# 2_classyTKL_SMK_matrix.net
KiCad netlist of a schematic drawn in Altium Designer
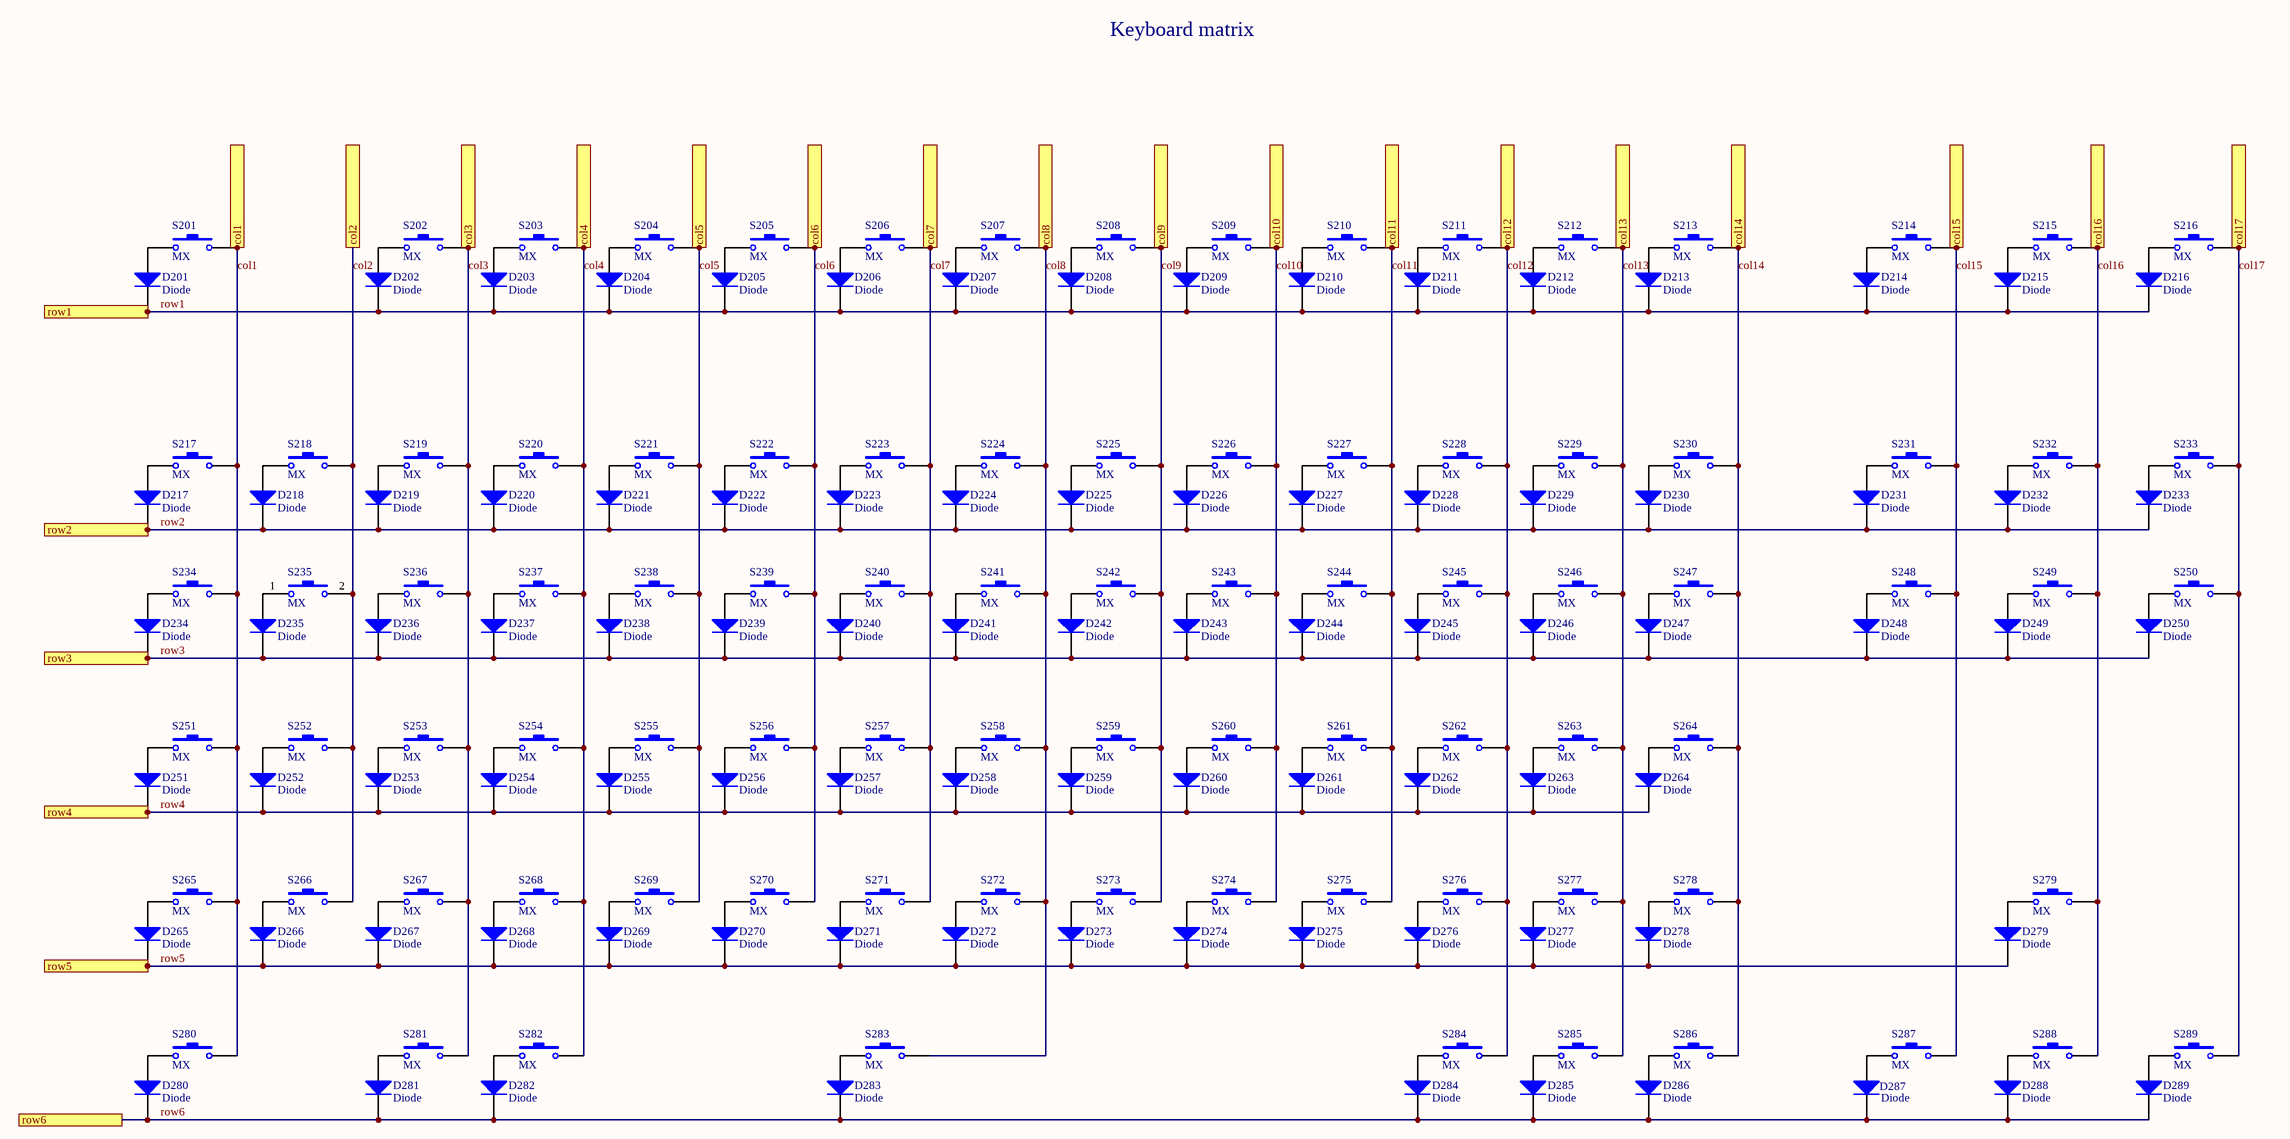
[diagram p0: 2_classyTKL_SMK_matrix.SchDoc]

(export (version "E")
  (design (tool "Eeschema 10.0.6"))
  (components
    (comp (ref "D201")
      (value "Diode")
      (footprint "SOD-123")
      (description "Default Diode")
      (fields (field (name "LCSC PART #") "C81598") (field (name "MRF.PART") "1N4148W"))
      (libsource (lib "Miscellaneous Devices") (part "Diode"))
    )
    (comp (ref "D202")
      (value "Diode")
      (footprint "SOD-123")
      (description "Default Diode")
      (fields (field (name "LCSC PART #") "C81598") (field (name "MRF.PART") "1N4148W"))
      (libsource (lib "Miscellaneous Devices") (part "Diode"))
    )
    (comp (ref "D203")
      (value "Diode")
      (footprint "SOD-123")
      (description "Default Diode")
      (fields (field (name "LCSC PART #") "C81598") (field (name "MRF.PART") "1N4148W"))
      (libsource (lib "Miscellaneous Devices") (part "Diode"))
    )
    (comp (ref "D204")
      (value "Diode")
      (footprint "SOD-123")
      (description "Default Diode")
      (fields (field (name "LCSC PART #") "C81598") (field (name "MRF.PART") "1N4148W"))
      (libsource (lib "Miscellaneous Devices") (part "Diode"))
    )
    (comp (ref "D205")
      (value "Diode")
      (footprint "SOD-123")
      (description "Default Diode")
      (fields (field (name "LCSC PART #") "C81598") (field (name "MRF.PART") "1N4148W"))
      (libsource (lib "Miscellaneous Devices") (part "Diode"))
    )
    (comp (ref "D206")
      (value "Diode")
      (footprint "SOD-123")
      (description "Default Diode")
      (fields (field (name "LCSC PART #") "C81598") (field (name "MRF.PART") "1N4148W"))
      (libsource (lib "Miscellaneous Devices") (part "Diode"))
    )
    (comp (ref "D207")
      (value "Diode")
      (footprint "SOD-123")
      (description "Default Diode")
      (fields (field (name "LCSC PART #") "C81598") (field (name "MRF.PART") "1N4148W"))
      (libsource (lib "Miscellaneous Devices") (part "Diode"))
    )
    (comp (ref "D208")
      (value "Diode")
      (footprint "SOD-123")
      (description "Default Diode")
      (fields (field (name "LCSC PART #") "C81598") (field (name "MRF.PART") "1N4148W"))
      (libsource (lib "Miscellaneous Devices") (part "Diode"))
    )
    (comp (ref "D209")
      (value "Diode")
      (footprint "SOD-123")
      (description "Default Diode")
      (fields (field (name "LCSC PART #") "C81598") (field (name "MRF.PART") "1N4148W"))
      (libsource (lib "Miscellaneous Devices") (part "Diode"))
    )
    (comp (ref "D210")
      (value "Diode")
      (footprint "SOD-123")
      (description "Default Diode")
      (fields (field (name "LCSC PART #") "C81598") (field (name "MRF.PART") "1N4148W"))
      (libsource (lib "Miscellaneous Devices") (part "Diode"))
    )
    (comp (ref "D211")
      (value "Diode")
      (footprint "SOD-123")
      (description "Default Diode")
      (fields (field (name "LCSC PART #") "C81598") (field (name "MRF.PART") "1N4148W"))
      (libsource (lib "Miscellaneous Devices") (part "Diode"))
    )
    (comp (ref "D212")
      (value "Diode")
      (footprint "SOD-123")
      (description "Default Diode")
      (fields (field (name "LCSC PART #") "C81598") (field (name "MRF.PART") "1N4148W"))
      (libsource (lib "Miscellaneous Devices") (part "Diode"))
    )
    (comp (ref "D213")
      (value "Diode")
      (footprint "SOD-123")
      (description "Default Diode")
      (fields (field (name "LCSC PART #") "C81598") (field (name "MRF.PART") "1N4148W"))
      (libsource (lib "Miscellaneous Devices") (part "Diode"))
    )
    (comp (ref "D214")
      (value "Diode")
      (footprint "SOD-123")
      (description "Default Diode")
      (fields (field (name "LCSC PART #") "C81598") (field (name "MRF.PART") "1N4148W"))
      (libsource (lib "Miscellaneous Devices") (part "Diode"))
    )
    (comp (ref "D215")
      (value "Diode")
      (footprint "SOD-123")
      (description "Default Diode")
      (fields (field (name "LCSC PART #") "C81598") (field (name "MRF.PART") "1N4148W"))
      (libsource (lib "Miscellaneous Devices") (part "Diode"))
    )
    (comp (ref "D216")
      (value "Diode")
      (footprint "SOD-123")
      (description "Default Diode")
      (fields (field (name "LCSC PART #") "C81598") (field (name "MRF.PART") "1N4148W"))
      (libsource (lib "Miscellaneous Devices") (part "Diode"))
    )
    (comp (ref "D217")
      (value "Diode")
      (footprint "SOD-123")
      (description "Default Diode")
      (fields (field (name "LCSC PART #") "C81598") (field (name "MRF.PART") "1N4148W"))
      (libsource (lib "Miscellaneous Devices") (part "Diode"))
    )
    (comp (ref "D218")
      (value "Diode")
      (footprint "SOD-123")
      (description "Default Diode")
      (fields (field (name "LCSC PART #") "C81598") (field (name "MRF.PART") "1N4148W"))
      (libsource (lib "Miscellaneous Devices") (part "Diode"))
    )
    (comp (ref "D219")
      (value "Diode")
      (footprint "SOD-123")
      (description "Default Diode")
      (fields (field (name "LCSC PART #") "C81598") (field (name "MRF.PART") "1N4148W"))
      (libsource (lib "Miscellaneous Devices") (part "Diode"))
    )
    (comp (ref "D220")
      (value "Diode")
      (footprint "SOD-123")
      (description "Default Diode")
      (fields (field (name "LCSC PART #") "C81598") (field (name "MRF.PART") "1N4148W"))
      (libsource (lib "Miscellaneous Devices") (part "Diode"))
    )
    (comp (ref "D221")
      (value "Diode")
      (footprint "SOD-123")
      (description "Default Diode")
      (fields (field (name "LCSC PART #") "C81598") (field (name "MRF.PART") "1N4148W"))
      (libsource (lib "Miscellaneous Devices") (part "Diode"))
    )
    (comp (ref "D222")
      (value "Diode")
      (footprint "SOD-123")
      (description "Default Diode")
      (fields (field (name "LCSC PART #") "C81598") (field (name "MRF.PART") "1N4148W"))
      (libsource (lib "Miscellaneous Devices") (part "Diode"))
    )
    (comp (ref "D223")
      (value "Diode")
      (footprint "SOD-123")
      (description "Default Diode")
      (fields (field (name "LCSC PART #") "C81598") (field (name "MRF.PART") "1N4148W"))
      (libsource (lib "Miscellaneous Devices") (part "Diode"))
    )
    (comp (ref "D224")
      (value "Diode")
      (footprint "SOD-123")
      (description "Default Diode")
      (fields (field (name "LCSC PART #") "C81598") (field (name "MRF.PART") "1N4148W"))
      (libsource (lib "Miscellaneous Devices") (part "Diode"))
    )
    (comp (ref "D225")
      (value "Diode")
      (footprint "SOD-123")
      (description "Default Diode")
      (fields (field (name "LCSC PART #") "C81598") (field (name "MRF.PART") "1N4148W"))
      (libsource (lib "Miscellaneous Devices") (part "Diode"))
    )
    (comp (ref "D226")
      (value "Diode")
      (footprint "SOD-123")
      (description "Default Diode")
      (fields (field (name "LCSC PART #") "C81598") (field (name "MRF.PART") "1N4148W"))
      (libsource (lib "Miscellaneous Devices") (part "Diode"))
    )
    (comp (ref "D227")
      (value "Diode")
      (footprint "SOD-123")
      (description "Default Diode")
      (fields (field (name "LCSC PART #") "C81598") (field (name "MRF.PART") "1N4148W"))
      (libsource (lib "Miscellaneous Devices") (part "Diode"))
    )
    (comp (ref "D228")
      (value "Diode")
      (footprint "SOD-123")
      (description "Default Diode")
      (fields (field (name "LCSC PART #") "C81598") (field (name "MRF.PART") "1N4148W"))
      (libsource (lib "Miscellaneous Devices") (part "Diode"))
    )
    (comp (ref "D229")
      (value "Diode")
      (footprint "SOD-123")
      (description "Default Diode")
      (fields (field (name "LCSC PART #") "C81598") (field (name "MRF.PART") "1N4148W"))
      (libsource (lib "Miscellaneous Devices") (part "Diode"))
    )
    (comp (ref "D230")
      (value "Diode")
      (footprint "SOD-123")
      (description "Default Diode")
      (fields (field (name "LCSC PART #") "C81598") (field (name "MRF.PART") "1N4148W"))
      (libsource (lib "Miscellaneous Devices") (part "Diode"))
    )
    (comp (ref "D231")
      (value "Diode")
      (footprint "SOD-123")
      (description "Default Diode")
      (fields (field (name "LCSC PART #") "C81598") (field (name "MRF.PART") "1N4148W"))
      (libsource (lib "Miscellaneous Devices") (part "Diode"))
    )
    (comp (ref "D232")
      (value "Diode")
      (footprint "SOD-123")
      (description "Default Diode")
      (fields (field (name "LCSC PART #") "C81598") (field (name "MRF.PART") "1N4148W"))
      (libsource (lib "Miscellaneous Devices") (part "Diode"))
    )
    (comp (ref "D233")
      (value "Diode")
      (footprint "SOD-123")
      (description "Default Diode")
      (fields (field (name "LCSC PART #") "C81598") (field (name "MRF.PART") "1N4148W"))
      (libsource (lib "Miscellaneous Devices") (part "Diode"))
    )
    (comp (ref "D234")
      (value "Diode")
      (footprint "SOD-123")
      (description "Default Diode")
      (fields (field (name "LCSC PART #") "C81598") (field (name "MRF.PART") "1N4148W"))
      (libsource (lib "Miscellaneous Devices") (part "Diode"))
    )
    (comp (ref "D235")
      (value "Diode")
      (footprint "SOD-123")
      (description "Default Diode")
      (fields (field (name "LCSC PART #") "C81598") (field (name "MRF.PART") "1N4148W"))
      (libsource (lib "Miscellaneous Devices") (part "Diode"))
    )
    (comp (ref "D236")
      (value "Diode")
      (footprint "SOD-123")
      (description "Default Diode")
      (fields (field (name "LCSC PART #") "C81598") (field (name "MRF.PART") "1N4148W"))
      (libsource (lib "Miscellaneous Devices") (part "Diode"))
    )
    (comp (ref "D237")
      (value "Diode")
      (footprint "SOD-123")
      (description "Default Diode")
      (fields (field (name "LCSC PART #") "C81598") (field (name "MRF.PART") "1N4148W"))
      (libsource (lib "Miscellaneous Devices") (part "Diode"))
    )
    (comp (ref "D238")
      (value "Diode")
      (footprint "SOD-123")
      (description "Default Diode")
      (fields (field (name "LCSC PART #") "C81598") (field (name "MRF.PART") "1N4148W"))
      (libsource (lib "Miscellaneous Devices") (part "Diode"))
    )
    (comp (ref "D239")
      (value "Diode")
      (footprint "SOD-123")
      (description "Default Diode")
      (fields (field (name "LCSC PART #") "C81598") (field (name "MRF.PART") "1N4148W"))
      (libsource (lib "Miscellaneous Devices") (part "Diode"))
    )
    (comp (ref "D240")
      (value "Diode")
      (footprint "SOD-123")
      (description "Default Diode")
      (fields (field (name "LCSC PART #") "C81598") (field (name "MRF.PART") "1N4148W"))
      (libsource (lib "Miscellaneous Devices") (part "Diode"))
    )
    (comp (ref "D241")
      (value "Diode")
      (footprint "SOD-123")
      (description "Default Diode")
      (fields (field (name "LCSC PART #") "C81598") (field (name "MRF.PART") "1N4148W"))
      (libsource (lib "Miscellaneous Devices") (part "Diode"))
    )
    (comp (ref "D242")
      (value "Diode")
      (footprint "SOD-123")
      (description "Default Diode")
      (fields (field (name "LCSC PART #") "C81598") (field (name "MRF.PART") "1N4148W"))
      (libsource (lib "Miscellaneous Devices") (part "Diode"))
    )
    (comp (ref "D243")
      (value "Diode")
      (footprint "SOD-123")
      (description "Default Diode")
      (fields (field (name "LCSC PART #") "C81598") (field (name "MRF.PART") "1N4148W"))
      (libsource (lib "Miscellaneous Devices") (part "Diode"))
    )
    (comp (ref "D244")
      (value "Diode")
      (footprint "SOD-123")
      (description "Default Diode")
      (fields (field (name "LCSC PART #") "C81598") (field (name "MRF.PART") "1N4148W"))
      (libsource (lib "Miscellaneous Devices") (part "Diode"))
    )
    (comp (ref "D245")
      (value "Diode")
      (footprint "SOD-123")
      (description "Default Diode")
      (fields (field (name "LCSC PART #") "C81598") (field (name "MRF.PART") "1N4148W"))
      (libsource (lib "Miscellaneous Devices") (part "Diode"))
    )
    (comp (ref "D246")
      (value "Diode")
      (footprint "SOD-123")
      (description "Default Diode")
      (fields (field (name "LCSC PART #") "C81598") (field (name "MRF.PART") "1N4148W"))
      (libsource (lib "Miscellaneous Devices") (part "Diode"))
    )
    (comp (ref "D247")
      (value "Diode")
      (footprint "SOD-123")
      (description "Default Diode")
      (fields (field (name "LCSC PART #") "C81598") (field (name "MRF.PART") "1N4148W"))
      (libsource (lib "Miscellaneous Devices") (part "Diode"))
    )
    (comp (ref "D248")
      (value "Diode")
      (footprint "SOD-123")
      (description "Default Diode")
      (fields (field (name "LCSC PART #") "C81598") (field (name "MRF.PART") "1N4148W"))
      (libsource (lib "Miscellaneous Devices") (part "Diode"))
    )
    (comp (ref "D249")
      (value "Diode")
      (footprint "SOD-123")
      (description "Default Diode")
      (fields (field (name "LCSC PART #") "C81598") (field (name "MRF.PART") "1N4148W"))
      (libsource (lib "Miscellaneous Devices") (part "Diode"))
    )
    (comp (ref "D250")
      (value "Diode")
      (footprint "SOD-123")
      (description "Default Diode")
      (fields (field (name "LCSC PART #") "C81598") (field (name "MRF.PART") "1N4148W"))
      (libsource (lib "Miscellaneous Devices") (part "Diode"))
    )
    (comp (ref "D251")
      (value "Diode")
      (footprint "SOD-123")
      (description "Default Diode")
      (fields (field (name "LCSC PART #") "C81598") (field (name "MRF.PART") "1N4148W"))
      (libsource (lib "Miscellaneous Devices") (part "Diode"))
    )
    (comp (ref "D252")
      (value "Diode")
      (footprint "SOD-123")
      (description "Default Diode")
      (fields (field (name "LCSC PART #") "C81598") (field (name "MRF.PART") "1N4148W"))
      (libsource (lib "Miscellaneous Devices") (part "Diode"))
    )
    (comp (ref "D253")
      (value "Diode")
      (footprint "SOD-123")
      (description "Default Diode")
      (fields (field (name "LCSC PART #") "C81598") (field (name "MRF.PART") "1N4148W"))
      (libsource (lib "Miscellaneous Devices") (part "Diode"))
    )
    (comp (ref "D254")
      (value "Diode")
      (footprint "SOD-123")
      (description "Default Diode")
      (fields (field (name "LCSC PART #") "C81598") (field (name "MRF.PART") "1N4148W"))
      (libsource (lib "Miscellaneous Devices") (part "Diode"))
    )
    (comp (ref "D255")
      (value "Diode")
      (footprint "SOD-123")
      (description "Default Diode")
      (fields (field (name "LCSC PART #") "C81598") (field (name "MRF.PART") "1N4148W"))
      (libsource (lib "Miscellaneous Devices") (part "Diode"))
    )
    (comp (ref "D256")
      (value "Diode")
      (footprint "SOD-123")
      (description "Default Diode")
      (fields (field (name "LCSC PART #") "C81598") (field (name "MRF.PART") "1N4148W"))
      (libsource (lib "Miscellaneous Devices") (part "Diode"))
    )
    (comp (ref "D257")
      (value "Diode")
      (footprint "SOD-123")
      (description "Default Diode")
      (fields (field (name "LCSC PART #") "C81598") (field (name "MRF.PART") "1N4148W"))
      (libsource (lib "Miscellaneous Devices") (part "Diode"))
    )
    (comp (ref "D258")
      (value "Diode")
      (footprint "SOD-123")
      (description "Default Diode")
      (fields (field (name "LCSC PART #") "C81598") (field (name "MRF.PART") "1N4148W"))
      (libsource (lib "Miscellaneous Devices") (part "Diode"))
    )
    (comp (ref "D259")
      (value "Diode")
      (footprint "SOD-123")
      (description "Default Diode")
      (fields (field (name "LCSC PART #") "C81598") (field (name "MRF.PART") "1N4148W"))
      (libsource (lib "Miscellaneous Devices") (part "Diode"))
    )
    (comp (ref "D260")
      (value "Diode")
      (footprint "SOD-123")
      (description "Default Diode")
      (fields (field (name "LCSC PART #") "C81598") (field (name "MRF.PART") "1N4148W"))
      (libsource (lib "Miscellaneous Devices") (part "Diode"))
    )
    (comp (ref "D261")
      (value "Diode")
      (footprint "SOD-123")
      (description "Default Diode")
      (fields (field (name "LCSC PART #") "C81598") (field (name "MRF.PART") "1N4148W"))
      (libsource (lib "Miscellaneous Devices") (part "Diode"))
    )
    (comp (ref "D262")
      (value "Diode")
      (footprint "SOD-123")
      (description "Default Diode")
      (fields (field (name "LCSC PART #") "C81598") (field (name "MRF.PART") "1N4148W"))
      (libsource (lib "Miscellaneous Devices") (part "Diode"))
    )
    (comp (ref "D263")
      (value "Diode")
      (footprint "SOD-123")
      (description "Default Diode")
      (fields (field (name "LCSC PART #") "C81598") (field (name "MRF.PART") "1N4148W"))
      (libsource (lib "Miscellaneous Devices") (part "Diode"))
    )
    (comp (ref "D264")
      (value "Diode")
      (footprint "SOD-123")
      (description "Default Diode")
      (fields (field (name "LCSC PART #") "C81598") (field (name "MRF.PART") "1N4148W"))
      (libsource (lib "Miscellaneous Devices") (part "Diode"))
    )
    (comp (ref "D265")
      (value "Diode")
      (footprint "SOD-123")
      (description "Default Diode")
      (fields (field (name "LCSC PART #") "C81598") (field (name "MRF.PART") "1N4148W"))
      (libsource (lib "Miscellaneous Devices") (part "Diode"))
    )
    (comp (ref "D266")
      (value "Diode")
      (footprint "SOD-123")
      (description "Default Diode")
      (fields (field (name "LCSC PART #") "C81598") (field (name "MRF.PART") "1N4148W"))
      (libsource (lib "Miscellaneous Devices") (part "Diode"))
    )
    (comp (ref "D267")
      (value "Diode")
      (footprint "SOD-123")
      (description "Default Diode")
      (fields (field (name "LCSC PART #") "C81598") (field (name "MRF.PART") "1N4148W"))
      (libsource (lib "Miscellaneous Devices") (part "Diode"))
    )
    (comp (ref "D268")
      (value "Diode")
      (footprint "SOD-123")
      (description "Default Diode")
      (fields (field (name "LCSC PART #") "C81598") (field (name "MRF.PART") "1N4148W"))
      (libsource (lib "Miscellaneous Devices") (part "Diode"))
    )
    (comp (ref "D269")
      (value "Diode")
      (footprint "SOD-123")
      (description "Default Diode")
      (fields (field (name "LCSC PART #") "C81598") (field (name "MRF.PART") "1N4148W"))
      (libsource (lib "Miscellaneous Devices") (part "Diode"))
    )
    (comp (ref "D270")
      (value "Diode")
      (footprint "SOD-123")
      (description "Default Diode")
      (fields (field (name "LCSC PART #") "C81598") (field (name "MRF.PART") "1N4148W"))
      (libsource (lib "Miscellaneous Devices") (part "Diode"))
    )
    (comp (ref "D271")
      (value "Diode")
      (footprint "SOD-123")
      (description "Default Diode")
      (fields (field (name "LCSC PART #") "C81598") (field (name "MRF.PART") "1N4148W"))
      (libsource (lib "Miscellaneous Devices") (part "Diode"))
    )
    (comp (ref "D272")
      (value "Diode")
      (footprint "SOD-123")
      (description "Default Diode")
      (fields (field (name "LCSC PART #") "C81598") (field (name "MRF.PART") "1N4148W"))
      (libsource (lib "Miscellaneous Devices") (part "Diode"))
    )
    (comp (ref "D273")
      (value "Diode")
      (footprint "SOD-123")
      (description "Default Diode")
      (fields (field (name "LCSC PART #") "C81598") (field (name "MRF.PART") "1N4148W"))
      (libsource (lib "Miscellaneous Devices") (part "Diode"))
    )
    (comp (ref "D274")
      (value "Diode")
      (footprint "SOD-123")
      (description "Default Diode")
      (fields (field (name "LCSC PART #") "C81598") (field (name "MRF.PART") "1N4148W"))
      (libsource (lib "Miscellaneous Devices") (part "Diode"))
    )
    (comp (ref "D275")
      (value "Diode")
      (footprint "SOD-123")
      (description "Default Diode")
      (fields (field (name "LCSC PART #") "C81598") (field (name "MRF.PART") "1N4148W"))
      (libsource (lib "Miscellaneous Devices") (part "Diode"))
    )
    (comp (ref "D276")
      (value "Diode")
      (footprint "SOD-123")
      (description "Default Diode")
      (fields (field (name "LCSC PART #") "C81598") (field (name "MRF.PART") "1N4148W"))
      (libsource (lib "Miscellaneous Devices") (part "Diode"))
    )
    (comp (ref "D277")
      (value "Diode")
      (footprint "SOD-123")
      (description "Default Diode")
      (fields (field (name "LCSC PART #") "C81598") (field (name "MRF.PART") "1N4148W"))
      (libsource (lib "Miscellaneous Devices") (part "Diode"))
    )
    (comp (ref "D278")
      (value "Diode")
      (footprint "SOD-123")
      (description "Default Diode")
      (fields (field (name "LCSC PART #") "C81598") (field (name "MRF.PART") "1N4148W"))
      (libsource (lib "Miscellaneous Devices") (part "Diode"))
    )
    (comp (ref "D279")
      (value "Diode")
      (footprint "SOD-123")
      (description "Default Diode")
      (fields (field (name "LCSC PART #") "C81598") (field (name "MRF.PART") "1N4148W"))
      (libsource (lib "Miscellaneous Devices") (part "Diode"))
    )
    (comp (ref "D280")
      (value "Diode")
      (footprint "SOD-123")
      (description "Default Diode")
      (fields (field (name "LCSC PART #") "C81598") (field (name "MRF.PART") "1N4148W"))
      (libsource (lib "Miscellaneous Devices") (part "Diode"))
    )
    (comp (ref "D281")
      (value "Diode")
      (footprint "SOD-123")
      (description "Default Diode")
      (fields (field (name "LCSC PART #") "C81598") (field (name "MRF.PART") "1N4148W"))
      (libsource (lib "Miscellaneous Devices") (part "Diode"))
    )
    (comp (ref "D282")
      (value "Diode")
      (footprint "SOD-123")
      (description "Default Diode")
      (fields (field (name "LCSC PART #") "C81598") (field (name "MRF.PART") "1N4148W"))
      (libsource (lib "Miscellaneous Devices") (part "Diode"))
    )
    (comp (ref "D283")
      (value "Diode")
      (footprint "SOD-123")
      (description "Default Diode")
      (fields (field (name "LCSC PART #") "C81598") (field (name "MRF.PART") "1N4148W"))
      (libsource (lib "Miscellaneous Devices") (part "Diode"))
    )
    (comp (ref "D284")
      (value "Diode")
      (footprint "SOD-123")
      (description "Default Diode")
      (fields (field (name "LCSC PART #") "C81598") (field (name "MRF.PART") "1N4148W"))
      (libsource (lib "Miscellaneous Devices") (part "Diode"))
    )
    (comp (ref "D285")
      (value "Diode")
      (footprint "SOD-123")
      (description "Default Diode")
      (fields (field (name "LCSC PART #") "C81598") (field (name "MRF.PART") "1N4148W"))
      (libsource (lib "Miscellaneous Devices") (part "Diode"))
    )
    (comp (ref "D286")
      (value "Diode")
      (footprint "SOD-123")
      (description "Default Diode")
      (fields (field (name "LCSC PART #") "C81598") (field (name "MRF.PART") "1N4148W"))
      (libsource (lib "Miscellaneous Devices") (part "Diode"))
    )
    (comp (ref "D287")
      (value "Diode")
      (footprint "SOD-123")
      (description "Default Diode")
      (fields (field (name "LCSC PART #") "C81598") (field (name "MRF.PART") "1N4148W"))
      (libsource (lib "Miscellaneous Devices") (part "Diode"))
    )
    (comp (ref "D288")
      (value "Diode")
      (footprint "SOD-123")
      (description "Default Diode")
      (fields (field (name "LCSC PART #") "C81598") (field (name "MRF.PART") "1N4148W"))
      (libsource (lib "Miscellaneous Devices") (part "Diode"))
    )
    (comp (ref "D289")
      (value "Diode")
      (footprint "SOD-123")
      (description "Default Diode")
      (fields (field (name "LCSC PART #") "C81598") (field (name "MRF.PART") "1N4148W"))
      (libsource (lib "Miscellaneous Devices") (part "Diode"))
    )
    (comp (ref "S201")
      (value "MX")
      (footprint "SMK-switch - switched polarity")
      (description "Switch")
      (libsource (lib "Miscellaneous Devices") (part "SW-PB"))
    )
    (comp (ref "S202")
      (value "MX")
      (footprint "SMK-switch")
      (description "Switch")
      (libsource (lib "Miscellaneous Devices") (part "SW-PB"))
    )
    (comp (ref "S203")
      (value "MX")
      (footprint "SMK-switch")
      (description "Switch")
      (libsource (lib "Miscellaneous Devices") (part "SW-PB"))
    )
    (comp (ref "S204")
      (value "MX")
      (footprint "SMK-switch")
      (description "Switch")
      (libsource (lib "Miscellaneous Devices") (part "SW-PB"))
    )
    (comp (ref "S205")
      (value "MX")
      (footprint "SMK-switch - switched polarity")
      (description "Switch")
      (libsource (lib "Miscellaneous Devices") (part "SW-PB"))
    )
    (comp (ref "S206")
      (value "MX")
      (footprint "SMK-switch")
      (description "Switch")
      (libsource (lib "Miscellaneous Devices") (part "SW-PB"))
    )
    (comp (ref "S207")
      (value "MX")
      (footprint "SMK-switch")
      (description "Switch")
      (libsource (lib "Miscellaneous Devices") (part "SW-PB"))
    )
    (comp (ref "S208")
      (value "MX")
      (footprint "SMK-switch")
      (description "Switch")
      (libsource (lib "Miscellaneous Devices") (part "SW-PB"))
    )
    (comp (ref "S209")
      (value "MX")
      (footprint "SMK-switch")
      (description "Switch")
      (libsource (lib "Miscellaneous Devices") (part "SW-PB"))
    )
    (comp (ref "S210")
      (value "MX")
      (footprint "SMK-switch")
      (description "Switch")
      (libsource (lib "Miscellaneous Devices") (part "SW-PB"))
    )
    (comp (ref "S211")
      (value "MX")
      (footprint "SMK-switch")
      (description "Switch")
      (libsource (lib "Miscellaneous Devices") (part "SW-PB"))
    )
    (comp (ref "S212")
      (value "MX")
      (footprint "SMK-switch")
      (description "Switch")
      (libsource (lib "Miscellaneous Devices") (part "SW-PB"))
    )
    (comp (ref "S213")
      (value "MX")
      (footprint "SMK-switch")
      (description "Switch")
      (libsource (lib "Miscellaneous Devices") (part "SW-PB"))
    )
    (comp (ref "S214")
      (value "MX")
      (footprint "SMK-switch")
      (description "Switch")
      (libsource (lib "Miscellaneous Devices") (part "SW-PB"))
    )
    (comp (ref "S215")
      (value "MX")
      (footprint "SMK-switch")
      (description "Switch")
      (libsource (lib "Miscellaneous Devices") (part "SW-PB"))
    )
    (comp (ref "S216")
      (value "MX")
      (footprint "SMK-switch")
      (description "Switch")
      (libsource (lib "Miscellaneous Devices") (part "SW-PB"))
    )
    (comp (ref "S217")
      (value "MX")
      (footprint "SMK-switch - switched polarity")
      (description "Switch")
      (libsource (lib "Miscellaneous Devices") (part "SW-PB"))
    )
    (comp (ref "S218")
      (value "MX")
      (footprint "SMK-switch - switched polarity")
      (description "Switch")
      (libsource (lib "Miscellaneous Devices") (part "SW-PB"))
    )
    (comp (ref "S219")
      (value "MX")
      (footprint "SMK-switch - switched polarity")
      (description "Switch")
      (libsource (lib "Miscellaneous Devices") (part "SW-PB"))
    )
    (comp (ref "S220")
      (value "MX")
      (footprint "SMK-switch - switched polarity")
      (description "Switch")
      (libsource (lib "Miscellaneous Devices") (part "SW-PB"))
    )
    (comp (ref "S221")
      (value "MX")
      (footprint "SMK-switch - switched polarity")
      (description "Switch")
      (libsource (lib "Miscellaneous Devices") (part "SW-PB"))
    )
    (comp (ref "S222")
      (value "MX")
      (footprint "SMK-switch - switched polarity")
      (description "Switch")
      (libsource (lib "Miscellaneous Devices") (part "SW-PB"))
    )
    (comp (ref "S223")
      (value "MX")
      (footprint "SMK-switch - switched polarity")
      (description "Switch")
      (libsource (lib "Miscellaneous Devices") (part "SW-PB"))
    )
    (comp (ref "S224")
      (value "MX")
      (footprint "SMK-switch - switched polarity")
      (description "Switch")
      (libsource (lib "Miscellaneous Devices") (part "SW-PB"))
    )
    (comp (ref "S225")
      (value "MX")
      (footprint "SMK-switch - switched polarity")
      (description "Switch")
      (libsource (lib "Miscellaneous Devices") (part "SW-PB"))
    )
    (comp (ref "S226")
      (value "MX")
      (footprint "SMK-switch - switched polarity")
      (description "Switch")
      (libsource (lib "Miscellaneous Devices") (part "SW-PB"))
    )
    (comp (ref "S227")
      (value "MX")
      (footprint "SMK-switch - switched polarity")
      (description "Switch")
      (libsource (lib "Miscellaneous Devices") (part "SW-PB"))
    )
    (comp (ref "S228")
      (value "MX")
      (footprint "SMK-switch - switched polarity")
      (description "Switch")
      (libsource (lib "Miscellaneous Devices") (part "SW-PB"))
    )
    (comp (ref "S229")
      (value "MX")
      (footprint "SMK-switch - switched polarity")
      (description "Switch")
      (libsource (lib "Miscellaneous Devices") (part "SW-PB"))
    )
    (comp (ref "S230")
      (value "MX")
      (footprint "SMK-switch")
      (description "Switch")
      (libsource (lib "Miscellaneous Devices") (part "SW-PB"))
    )
    (comp (ref "S231")
      (value "MX")
      (footprint "SMK-switch")
      (description "Switch")
      (libsource (lib "Miscellaneous Devices") (part "SW-PB"))
    )
    (comp (ref "S232")
      (value "MX")
      (footprint "SMK-switch")
      (description "Switch")
      (libsource (lib "Miscellaneous Devices") (part "SW-PB"))
    )
    (comp (ref "S233")
      (value "MX")
      (footprint "SMK-switch")
      (description "Switch")
      (libsource (lib "Miscellaneous Devices") (part "SW-PB"))
    )
    (comp (ref "S234")
      (value "MX")
      (footprint "SMK-switch - 1.5U")
      (description "TAB")
      (libsource (lib "Miscellaneous Devices") (part "SW-PB"))
    )
    (comp (ref "S235")
      (value "MX")
      (footprint "SMK-switch - switched polarity")
      (description "Switch")
      (libsource (lib "") (part "SW-PB_1"))
    )
    (comp (ref "S236")
      (value "MX")
      (footprint "SMK-switch - switched polarity")
      (description "Switch")
      (libsource (lib "Miscellaneous Devices") (part "SW-PB"))
    )
    (comp (ref "S237")
      (value "MX")
      (footprint "SMK-switch - switched polarity")
      (description "Switch")
      (libsource (lib "Miscellaneous Devices") (part "SW-PB"))
    )
    (comp (ref "S238")
      (value "MX")
      (footprint "SMK-switch - switched polarity")
      (description "Switch")
      (libsource (lib "Miscellaneous Devices") (part "SW-PB"))
    )
    (comp (ref "S239")
      (value "MX")
      (footprint "SMK-switch - switched polarity")
      (description "Switch")
      (libsource (lib "Miscellaneous Devices") (part "SW-PB"))
    )
    (comp (ref "S240")
      (value "MX")
      (footprint "SMK-switch - switched polarity")
      (description "Switch")
      (libsource (lib "Miscellaneous Devices") (part "SW-PB"))
    )
    (comp (ref "S241")
      (value "MX")
      (footprint "SMK-switch - switched polarity")
      (description "Switch")
      (libsource (lib "Miscellaneous Devices") (part "SW-PB"))
    )
    (comp (ref "S242")
      (value "MX")
      (footprint "SMK-switch - switched polarity")
      (description "Switch")
      (libsource (lib "Miscellaneous Devices") (part "SW-PB"))
    )
    (comp (ref "S243")
      (value "MX")
      (footprint "SMK-switch - switched polarity")
      (description "Switch")
      (libsource (lib "Miscellaneous Devices") (part "SW-PB"))
    )
    (comp (ref "S244")
      (value "MX")
      (footprint "SMK-switch - switched polarity")
      (description "Switch")
      (libsource (lib "Miscellaneous Devices") (part "SW-PB"))
    )
    (comp (ref "S245")
      (value "MX")
      (footprint "SMK-switch - switched polarity")
      (description "Switch")
      (libsource (lib "Miscellaneous Devices") (part "SW-PB"))
    )
    (comp (ref "S246")
      (value "MX")
      (footprint "SMK-switch - switched polarity")
      (description "Switch")
      (libsource (lib "Miscellaneous Devices") (part "SW-PB"))
    )
    (comp (ref "S247")
      (value "MX")
      (footprint "SMK-switch - PIPE_ISO_ENTER")
      (description "Switch")
      (libsource (lib "Miscellaneous Devices") (part "SW-PB"))
    )
    (comp (ref "S248")
      (value "MX")
      (footprint "SMK-switch")
      (description "Switch")
      (libsource (lib "Miscellaneous Devices") (part "SW-PB"))
    )
    (comp (ref "S249")
      (value "MX")
      (footprint "SMK-switch")
      (description "Switch")
      (libsource (lib "Miscellaneous Devices") (part "SW-PB"))
    )
    (comp (ref "S250")
      (value "MX")
      (footprint "SMK-switch")
      (description "Switch")
      (libsource (lib "Miscellaneous Devices") (part "SW-PB"))
    )
    (comp (ref "S251")
      (value "MX")
      (footprint "SMK-switch - CAPS")
      (description "Switch")
      (libsource (lib "Miscellaneous Devices") (part "SW-PB"))
    )
    (comp (ref "S252")
      (value "MX")
      (footprint "SMK-switch - switched polarity")
      (description "Switch")
      (libsource (lib "Miscellaneous Devices") (part "SW-PB"))
    )
    (comp (ref "S253")
      (value "MX")
      (footprint "SMK-switch - switched polarity")
      (description "Switch")
      (libsource (lib "Miscellaneous Devices") (part "SW-PB"))
    )
    (comp (ref "S254")
      (value "MX")
      (footprint "SMK-switch - switched polarity")
      (description "Switch")
      (libsource (lib "Miscellaneous Devices") (part "SW-PB"))
    )
    (comp (ref "S255")
      (value "MX")
      (footprint "SMK-switch - switched polarity")
      (description "Switch")
      (libsource (lib "Miscellaneous Devices") (part "SW-PB"))
    )
    (comp (ref "S256")
      (value "MX")
      (footprint "SMK-switch - switched polarity")
      (description "Switch")
      (libsource (lib "Miscellaneous Devices") (part "SW-PB"))
    )
    (comp (ref "S257")
      (value "MX")
      (footprint "SMK-switch - switched polarity")
      (description "Switch")
      (libsource (lib "Miscellaneous Devices") (part "SW-PB"))
    )
    (comp (ref "S258")
      (value "MX")
      (footprint "SMK-switch - switched polarity")
      (description "Switch")
      (libsource (lib "Miscellaneous Devices") (part "SW-PB"))
    )
    (comp (ref "S259")
      (value "MX")
      (footprint "SMK-switch - switched polarity")
      (description "Switch")
      (libsource (lib "Miscellaneous Devices") (part "SW-PB"))
    )
    (comp (ref "S260")
      (value "MX")
      (footprint "SMK-switch - switched polarity")
      (description "Switch")
      (libsource (lib "Miscellaneous Devices") (part "SW-PB"))
    )
    (comp (ref "S261")
      (value "MX")
      (footprint "SMK-switch - switched polarity")
      (description "Switch")
      (libsource (lib "Miscellaneous Devices") (part "SW-PB"))
    )
    (comp (ref "S262")
      (value "MX")
      (footprint "SMK-switch - switched polarity")
      (description "Switch")
      (libsource (lib "Miscellaneous Devices") (part "SW-PB"))
    )
    (comp (ref "S263")
      (value "MX")
      (footprint "SMK-switch - Enter_ANSI_ISO_KEY")
      (description "Switch")
      (libsource (lib "Miscellaneous Devices") (part "SW-PB"))
    )
    (comp (ref "S264")
      (value "MX")
      (footprint "SMK-switch - backspace")
      (description "Switch")
      (libsource (lib "Miscellaneous Devices") (part "SW-PB"))
    )
    (comp (ref "S265")
      (value "MX")
      (footprint "SMK-switch - Left shift v2")
      (description "Switch")
      (libsource (lib "Miscellaneous Devices") (part "SW-PB"))
    )
    (comp (ref "S266")
      (value "MX")
      (footprint "SMK-switch - switched polarity")
      (description "Switch")
      (libsource (lib "Miscellaneous Devices") (part "SW-PB"))
    )
    (comp (ref "S267")
      (value "MX")
      (footprint "SMK-switch - switched polarity")
      (description "Switch")
      (libsource (lib "Miscellaneous Devices") (part "SW-PB"))
    )
    (comp (ref "S268")
      (value "MX")
      (footprint "SMK-switch - switched polarity")
      (description "Switch")
      (libsource (lib "Miscellaneous Devices") (part "SW-PB"))
    )
    (comp (ref "S269")
      (value "MX")
      (footprint "SMK-switch - switched polarity")
      (description "Switch")
      (libsource (lib "Miscellaneous Devices") (part "SW-PB"))
    )
    (comp (ref "S270")
      (value "MX")
      (footprint "SMK-switch - switched polarity")
      (description "Switch")
      (libsource (lib "Miscellaneous Devices") (part "SW-PB"))
    )
    (comp (ref "S271")
      (value "MX")
      (footprint "SMK-switch - switched polarity")
      (description "Switch")
      (libsource (lib "Miscellaneous Devices") (part "SW-PB"))
    )
    (comp (ref "S272")
      (value "MX")
      (footprint "SMK-switch - switched polarity")
      (description "Switch")
      (libsource (lib "Miscellaneous Devices") (part "SW-PB"))
    )
    (comp (ref "S273")
      (value "MX")
      (footprint "SMK-switch - switched polarity")
      (description "Switch")
      (libsource (lib "Miscellaneous Devices") (part "SW-PB"))
    )
    (comp (ref "S274")
      (value "MX")
      (footprint "SMK-switch - switched polarity")
      (description "Switch")
      (libsource (lib "Miscellaneous Devices") (part "SW-PB"))
    )
    (comp (ref "S275")
      (value "MX")
      (footprint "SMK-switch - switched polarity")
      (description "Switch")
      (libsource (lib "Miscellaneous Devices") (part "SW-PB"))
    )
    (comp (ref "S276")
      (value "MX")
      (footprint "SMK-switch - switched polarity")
      (description "Switch")
      (libsource (lib "Miscellaneous Devices") (part "SW-PB"))
    )
    (comp (ref "S277")
      (value "MX")
      (footprint "SMK-switch - right shift v2")
      (description "Switch")
      (libsource (lib "Miscellaneous Devices") (part "SW-PB"))
    )
    (comp (ref "S278")
      (value "MX")
      (footprint "SMK-switch")
      (description "Switch")
      (libsource (lib "Miscellaneous Devices") (part "SW-PB"))
    )
    (comp (ref "S279")
      (value "MX")
      (footprint "SMK-switch")
      (description "Switch")
      (libsource (lib "Miscellaneous Devices") (part "SW-PB"))
    )
    (comp (ref "S280")
      (value "MX")
      (footprint "SMK-switch - 1.5U")
      (description "Switch")
      (libsource (lib "Miscellaneous Devices") (part "SW-PB"))
    )
    (comp (ref "S281")
      (value "MX")
      (footprint "SMK-switch")
      (description "Switch")
      (libsource (lib "Miscellaneous Devices") (part "SW-PB"))
    )
    (comp (ref "S282")
      (value "MX")
      (footprint "SMK-switch - 1.5U")
      (description "Switch")
      (libsource (lib "Miscellaneous Devices") (part "SW-PB"))
    )
    (comp (ref "S283")
      (value "MX")
      (footprint "SMK_MX-switch - 7u space")
      (description "Switch")
      (libsource (lib "Miscellaneous Devices") (part "SW-PB"))
    )
    (comp (ref "S284")
      (value "MX")
      (footprint "SMK-switch - 1.5U")
      (description "Switch")
      (libsource (lib "Miscellaneous Devices") (part "SW-PB"))
    )
    (comp (ref "S285")
      (value "MX")
      (footprint "SMK-switch")
      (description "Switch")
      (libsource (lib "Miscellaneous Devices") (part "SW-PB"))
    )
    (comp (ref "S286")
      (value "MX")
      (footprint "SMK-switch - 1.5U")
      (description "Switch")
      (libsource (lib "Miscellaneous Devices") (part "SW-PB"))
    )
    (comp (ref "S287")
      (value "MX")
      (footprint "SMK-switch")
      (description "Switch")
      (libsource (lib "Miscellaneous Devices") (part "SW-PB"))
    )
    (comp (ref "S288")
      (value "MX")
      (footprint "SMK-switch")
      (description "Switch")
      (libsource (lib "Miscellaneous Devices") (part "SW-PB"))
    )
    (comp (ref "S289")
      (value "MX")
      (footprint "SMK-switch")
      (description "Switch")
      (libsource (lib "Miscellaneous Devices") (part "SW-PB"))
    )
  )
  (nets
    (net (code "1") (name "/col1") (class "Default")
      (node (ref "S201") (pin "2") (pinfunction "2_2") (pintype "passive"))
      (node (ref "S217") (pin "2") (pinfunction "2_2") (pintype "passive"))
      (node (ref "S234") (pin "1") (pinfunction "1_1") (pintype "passive"))
      (node (ref "S251") (pin "2") (pinfunction "2_2") (pintype "passive"))
      (node (ref "S265") (pin "2") (pinfunction "2_2") (pintype "passive"))
      (node (ref "S280") (pin "1") (pinfunction "1_1") (pintype "passive"))
    )
    (net (code "2") (name "/col2") (class "Default")
      (node (ref "S218") (pin "2") (pinfunction "2_2") (pintype "passive"))
      (node (ref "S235") (pin "2") (pinfunction "2_2") (pintype "passive"))
      (node (ref "S252") (pin "2") (pinfunction "2_2") (pintype "passive"))
      (node (ref "S266") (pin "2") (pinfunction "2_2") (pintype "passive"))
    )
    (net (code "3") (name "/col3") (class "Default")
      (node (ref "S202") (pin "2") (pinfunction "2_2") (pintype "passive"))
      (node (ref "S219") (pin "2") (pinfunction "2_2") (pintype "passive"))
      (node (ref "S236") (pin "2") (pinfunction "2_2") (pintype "passive"))
      (node (ref "S253") (pin "2") (pinfunction "2_2") (pintype "passive"))
      (node (ref "S267") (pin "2") (pinfunction "2_2") (pintype "passive"))
      (node (ref "S281") (pin "2") (pinfunction "2_2") (pintype "passive"))
    )
    (net (code "4") (name "/col4") (class "Default")
      (node (ref "S203") (pin "2") (pinfunction "2_2") (pintype "passive"))
      (node (ref "S220") (pin "2") (pinfunction "2_2") (pintype "passive"))
      (node (ref "S237") (pin "2") (pinfunction "2_2") (pintype "passive"))
      (node (ref "S254") (pin "2") (pinfunction "2_2") (pintype "passive"))
      (node (ref "S268") (pin "2") (pinfunction "2_2") (pintype "passive"))
      (node (ref "S282") (pin "2") (pinfunction "2_2") (pintype "passive"))
    )
    (net (code "5") (name "/col5") (class "Default")
      (node (ref "S204") (pin "2") (pinfunction "2_2") (pintype "passive"))
      (node (ref "S221") (pin "2") (pinfunction "2_2") (pintype "passive"))
      (node (ref "S238") (pin "2") (pinfunction "2_2") (pintype "passive"))
      (node (ref "S255") (pin "2") (pinfunction "2_2") (pintype "passive"))
      (node (ref "S269") (pin "2") (pinfunction "2_2") (pintype "passive"))
    )
    (net (code "6") (name "/col6") (class "Default")
      (node (ref "S205") (pin "2") (pinfunction "2_2") (pintype "passive"))
      (node (ref "S222") (pin "2") (pinfunction "2_2") (pintype "passive"))
      (node (ref "S239") (pin "2") (pinfunction "2_2") (pintype "passive"))
      (node (ref "S256") (pin "2") (pinfunction "2_2") (pintype "passive"))
      (node (ref "S270") (pin "2") (pinfunction "2_2") (pintype "passive"))
    )
    (net (code "7") (name "/col7") (class "Default")
      (node (ref "S206") (pin "2") (pinfunction "2_2") (pintype "passive"))
      (node (ref "S223") (pin "2") (pinfunction "2_2") (pintype "passive"))
      (node (ref "S240") (pin "2") (pinfunction "2_2") (pintype "passive"))
      (node (ref "S257") (pin "2") (pinfunction "2_2") (pintype "passive"))
      (node (ref "S271") (pin "2") (pinfunction "2_2") (pintype "passive"))
    )
    (net (code "8") (name "/col8") (class "Default")
      (node (ref "S207") (pin "2") (pinfunction "2_2") (pintype "passive"))
      (node (ref "S224") (pin "2") (pinfunction "2_2") (pintype "passive"))
      (node (ref "S241") (pin "2") (pinfunction "2_2") (pintype "passive"))
      (node (ref "S258") (pin "2") (pinfunction "2_2") (pintype "passive"))
      (node (ref "S272") (pin "2") (pinfunction "2_2") (pintype "passive"))
      (node (ref "S283") (pin "2") (pinfunction "2_2") (pintype "passive"))
    )
    (net (code "9") (name "/col9") (class "Default")
      (node (ref "S208") (pin "2") (pinfunction "2_2") (pintype "passive"))
      (node (ref "S225") (pin "2") (pinfunction "2_2") (pintype "passive"))
      (node (ref "S242") (pin "2") (pinfunction "2_2") (pintype "passive"))
      (node (ref "S259") (pin "2") (pinfunction "2_2") (pintype "passive"))
      (node (ref "S273") (pin "2") (pinfunction "2_2") (pintype "passive"))
    )
    (net (code "10") (name "/col10") (class "Default")
      (node (ref "S209") (pin "2") (pinfunction "2_2") (pintype "passive"))
      (node (ref "S226") (pin "2") (pinfunction "2_2") (pintype "passive"))
      (node (ref "S243") (pin "2") (pinfunction "2_2") (pintype "passive"))
      (node (ref "S260") (pin "2") (pinfunction "2_2") (pintype "passive"))
      (node (ref "S274") (pin "2") (pinfunction "2_2") (pintype "passive"))
    )
    (net (code "11") (name "/col11") (class "Default")
      (node (ref "S210") (pin "2") (pinfunction "2_2") (pintype "passive"))
      (node (ref "S227") (pin "2") (pinfunction "2_2") (pintype "passive"))
      (node (ref "S244") (pin "2") (pinfunction "2_2") (pintype "passive"))
      (node (ref "S261") (pin "2") (pinfunction "2_2") (pintype "passive"))
      (node (ref "S275") (pin "2") (pinfunction "2_2") (pintype "passive"))
    )
    (net (code "12") (name "/col12") (class "Default")
      (node (ref "S211") (pin "2") (pinfunction "2_2") (pintype "passive"))
      (node (ref "S228") (pin "2") (pinfunction "2_2") (pintype "passive"))
      (node (ref "S245") (pin "2") (pinfunction "2_2") (pintype "passive"))
      (node (ref "S262") (pin "2") (pinfunction "2_2") (pintype "passive"))
      (node (ref "S276") (pin "2") (pinfunction "2_2") (pintype "passive"))
      (node (ref "S284") (pin "2") (pinfunction "2_2") (pintype "passive"))
    )
    (net (code "13") (name "/col13") (class "Default")
      (node (ref "S212") (pin "2") (pinfunction "2_2") (pintype "passive"))
      (node (ref "S229") (pin "2") (pinfunction "2_2") (pintype "passive"))
      (node (ref "S246") (pin "2") (pinfunction "2_2") (pintype "passive"))
      (node (ref "S263") (pin "2") (pinfunction "2_2") (pintype "passive"))
      (node (ref "S277") (pin "2") (pinfunction "2_2") (pintype "passive"))
      (node (ref "S285") (pin "2") (pinfunction "2_2") (pintype "passive"))
    )
    (net (code "14") (name "/col14") (class "Default")
      (node (ref "S213") (pin "2") (pinfunction "2_2") (pintype "passive"))
      (node (ref "S230") (pin "2") (pinfunction "2_2") (pintype "passive"))
      (node (ref "S247") (pin "2") (pinfunction "2_2") (pintype "passive"))
      (node (ref "S264") (pin "2") (pinfunction "2_2") (pintype "passive"))
      (node (ref "S278") (pin "2") (pinfunction "2_2") (pintype "passive"))
      (node (ref "S286") (pin "2") (pinfunction "2_2") (pintype "passive"))
    )
    (net (code "15") (name "/col15") (class "Default")
      (node (ref "S214") (pin "2") (pinfunction "2_2") (pintype "passive"))
      (node (ref "S231") (pin "2") (pinfunction "2_2") (pintype "passive"))
      (node (ref "S248") (pin "2") (pinfunction "2_2") (pintype "passive"))
      (node (ref "S287") (pin "2") (pinfunction "2_2") (pintype "passive"))
    )
    (net (code "16") (name "/col16") (class "Default")
      (node (ref "S215") (pin "2") (pinfunction "2_2") (pintype "passive"))
      (node (ref "S232") (pin "2") (pinfunction "2_2") (pintype "passive"))
      (node (ref "S249") (pin "2") (pinfunction "2_2") (pintype "passive"))
      (node (ref "S279") (pin "2") (pinfunction "2_2") (pintype "passive"))
      (node (ref "S288") (pin "2") (pinfunction "2_2") (pintype "passive"))
    )
    (net (code "17") (name "/col17") (class "Default")
      (node (ref "S216") (pin "2") (pinfunction "2_2") (pintype "passive"))
      (node (ref "S233") (pin "2") (pinfunction "2_2") (pintype "passive"))
      (node (ref "S250") (pin "2") (pinfunction "2_2") (pintype "passive"))
      (node (ref "S289") (pin "2") (pinfunction "2_2") (pintype "passive"))
    )
    (net (code "18") (name "/row1") (class "Default")
      (node (ref "D201") (pin "2") (pinfunction "K_2") (pintype "passive"))
      (node (ref "D202") (pin "2") (pinfunction "K_2") (pintype "passive"))
      (node (ref "D203") (pin "2") (pinfunction "K_2") (pintype "passive"))
      (node (ref "D204") (pin "2") (pinfunction "K_2") (pintype "passive"))
      (node (ref "D205") (pin "2") (pinfunction "K_2") (pintype "passive"))
      (node (ref "D206") (pin "2") (pinfunction "K_2") (pintype "passive"))
      (node (ref "D207") (pin "2") (pinfunction "K_2") (pintype "passive"))
      (node (ref "D208") (pin "2") (pinfunction "K_2") (pintype "passive"))
      (node (ref "D209") (pin "2") (pinfunction "K_2") (pintype "passive"))
      (node (ref "D210") (pin "2") (pinfunction "K_2") (pintype "passive"))
      (node (ref "D211") (pin "2") (pinfunction "K_2") (pintype "passive"))
      (node (ref "D212") (pin "2") (pinfunction "K_2") (pintype "passive"))
      (node (ref "D213") (pin "2") (pinfunction "K_2") (pintype "passive"))
      (node (ref "D214") (pin "2") (pinfunction "K_2") (pintype "passive"))
      (node (ref "D215") (pin "2") (pinfunction "K_2") (pintype "passive"))
      (node (ref "D216") (pin "2") (pinfunction "K_2") (pintype "passive"))
    )
    (net (code "19") (name "/row2") (class "Default")
      (node (ref "D217") (pin "2") (pinfunction "K_2") (pintype "passive"))
      (node (ref "D218") (pin "2") (pinfunction "K_2") (pintype "passive"))
      (node (ref "D219") (pin "2") (pinfunction "K_2") (pintype "passive"))
      (node (ref "D220") (pin "2") (pinfunction "K_2") (pintype "passive"))
      (node (ref "D221") (pin "2") (pinfunction "K_2") (pintype "passive"))
      (node (ref "D222") (pin "2") (pinfunction "K_2") (pintype "passive"))
      (node (ref "D223") (pin "2") (pinfunction "K_2") (pintype "passive"))
      (node (ref "D224") (pin "2") (pinfunction "K_2") (pintype "passive"))
      (node (ref "D225") (pin "2") (pinfunction "K_2") (pintype "passive"))
      (node (ref "D226") (pin "2") (pinfunction "K_2") (pintype "passive"))
      (node (ref "D227") (pin "2") (pinfunction "K_2") (pintype "passive"))
      (node (ref "D228") (pin "2") (pinfunction "K_2") (pintype "passive"))
      (node (ref "D229") (pin "2") (pinfunction "K_2") (pintype "passive"))
      (node (ref "D230") (pin "2") (pinfunction "K_2") (pintype "passive"))
      (node (ref "D231") (pin "2") (pinfunction "K_2") (pintype "passive"))
      (node (ref "D232") (pin "2") (pinfunction "K_2") (pintype "passive"))
      (node (ref "D233") (pin "2") (pinfunction "K_2") (pintype "passive"))
    )
    (net (code "20") (name "/row3") (class "Default")
      (node (ref "D234") (pin "2") (pinfunction "K_2") (pintype "passive"))
      (node (ref "D235") (pin "2") (pinfunction "K_2") (pintype "passive"))
      (node (ref "D236") (pin "2") (pinfunction "K_2") (pintype "passive"))
      (node (ref "D237") (pin "2") (pinfunction "K_2") (pintype "passive"))
      (node (ref "D238") (pin "2") (pinfunction "K_2") (pintype "passive"))
      (node (ref "D239") (pin "2") (pinfunction "K_2") (pintype "passive"))
      (node (ref "D240") (pin "2") (pinfunction "K_2") (pintype "passive"))
      (node (ref "D241") (pin "2") (pinfunction "K_2") (pintype "passive"))
      (node (ref "D242") (pin "2") (pinfunction "K_2") (pintype "passive"))
      (node (ref "D243") (pin "2") (pinfunction "K_2") (pintype "passive"))
      (node (ref "D244") (pin "2") (pinfunction "K_2") (pintype "passive"))
      (node (ref "D245") (pin "2") (pinfunction "K_2") (pintype "passive"))
      (node (ref "D246") (pin "2") (pinfunction "K_2") (pintype "passive"))
      (node (ref "D247") (pin "2") (pinfunction "K_2") (pintype "passive"))
      (node (ref "D248") (pin "2") (pinfunction "K_2") (pintype "passive"))
      (node (ref "D249") (pin "2") (pinfunction "K_2") (pintype "passive"))
      (node (ref "D250") (pin "2") (pinfunction "K_2") (pintype "passive"))
    )
    (net (code "21") (name "/row4") (class "Default")
      (node (ref "D251") (pin "2") (pinfunction "K_2") (pintype "passive"))
      (node (ref "D252") (pin "2") (pinfunction "K_2") (pintype "passive"))
      (node (ref "D253") (pin "2") (pinfunction "K_2") (pintype "passive"))
      (node (ref "D254") (pin "2") (pinfunction "K_2") (pintype "passive"))
      (node (ref "D255") (pin "2") (pinfunction "K_2") (pintype "passive"))
      (node (ref "D256") (pin "2") (pinfunction "K_2") (pintype "passive"))
      (node (ref "D257") (pin "2") (pinfunction "K_2") (pintype "passive"))
      (node (ref "D258") (pin "2") (pinfunction "K_2") (pintype "passive"))
      (node (ref "D259") (pin "2") (pinfunction "K_2") (pintype "passive"))
      (node (ref "D260") (pin "2") (pinfunction "K_2") (pintype "passive"))
      (node (ref "D261") (pin "2") (pinfunction "K_2") (pintype "passive"))
      (node (ref "D262") (pin "2") (pinfunction "K_2") (pintype "passive"))
      (node (ref "D263") (pin "2") (pinfunction "K_2") (pintype "passive"))
      (node (ref "D264") (pin "2") (pinfunction "K_2") (pintype "passive"))
    )
    (net (code "22") (name "/row5") (class "Default")
      (node (ref "D265") (pin "2") (pinfunction "K_2") (pintype "passive"))
      (node (ref "D266") (pin "2") (pinfunction "K_2") (pintype "passive"))
      (node (ref "D267") (pin "2") (pinfunction "K_2") (pintype "passive"))
      (node (ref "D268") (pin "2") (pinfunction "K_2") (pintype "passive"))
      (node (ref "D269") (pin "2") (pinfunction "K_2") (pintype "passive"))
      (node (ref "D270") (pin "2") (pinfunction "K_2") (pintype "passive"))
      (node (ref "D271") (pin "2") (pinfunction "K_2") (pintype "passive"))
      (node (ref "D272") (pin "2") (pinfunction "K_2") (pintype "passive"))
      (node (ref "D273") (pin "2") (pinfunction "K_2") (pintype "passive"))
      (node (ref "D274") (pin "2") (pinfunction "K_2") (pintype "passive"))
      (node (ref "D275") (pin "2") (pinfunction "K_2") (pintype "passive"))
      (node (ref "D276") (pin "2") (pinfunction "K_2") (pintype "passive"))
      (node (ref "D277") (pin "2") (pinfunction "K_2") (pintype "passive"))
      (node (ref "D278") (pin "2") (pinfunction "K_2") (pintype "passive"))
      (node (ref "D279") (pin "2") (pinfunction "K_2") (pintype "passive"))
    )
    (net (code "23") (name "/row6") (class "Default")
      (node (ref "D280") (pin "2") (pinfunction "K_2") (pintype "passive"))
      (node (ref "D281") (pin "2") (pinfunction "K_2") (pintype "passive"))
      (node (ref "D282") (pin "2") (pinfunction "K_2") (pintype "passive"))
      (node (ref "D283") (pin "2") (pinfunction "K_2") (pintype "passive"))
      (node (ref "D284") (pin "2") (pinfunction "K_2") (pintype "passive"))
      (node (ref "D285") (pin "2") (pinfunction "K_2") (pintype "passive"))
      (node (ref "D286") (pin "2") (pinfunction "K_2") (pintype "passive"))
      (node (ref "D287") (pin "2") (pinfunction "K_2") (pintype "passive"))
      (node (ref "D288") (pin "2") (pinfunction "K_2") (pintype "passive"))
      (node (ref "D289") (pin "2") (pinfunction "K_2") (pintype "passive"))
    )
    (net (code "24") (name "Net-(D201-A)") (class "Default")
      (node (ref "D201") (pin "1") (pinfunction "A_1") (pintype "passive"))
      (node (ref "S201") (pin "1") (pinfunction "1_1") (pintype "passive"))
    )
    (net (code "25") (name "Net-(D202-A)") (class "Default")
      (node (ref "D202") (pin "1") (pinfunction "A_1") (pintype "passive"))
      (node (ref "S202") (pin "1") (pinfunction "1_1") (pintype "passive"))
    )
    (net (code "26") (name "Net-(D203-A)") (class "Default")
      (node (ref "D203") (pin "1") (pinfunction "A_1") (pintype "passive"))
      (node (ref "S203") (pin "1") (pinfunction "1_1") (pintype "passive"))
    )
    (net (code "27") (name "Net-(D204-A)") (class "Default")
      (node (ref "D204") (pin "1") (pinfunction "A_1") (pintype "passive"))
      (node (ref "S204") (pin "1") (pinfunction "1_1") (pintype "passive"))
    )
    (net (code "28") (name "Net-(D205-A)") (class "Default")
      (node (ref "D205") (pin "1") (pinfunction "A_1") (pintype "passive"))
      (node (ref "S205") (pin "1") (pinfunction "1_1") (pintype "passive"))
    )
    (net (code "29") (name "Net-(D206-A)") (class "Default")
      (node (ref "D206") (pin "1") (pinfunction "A_1") (pintype "passive"))
      (node (ref "S206") (pin "1") (pinfunction "1_1") (pintype "passive"))
    )
    (net (code "30") (name "Net-(D207-A)") (class "Default")
      (node (ref "D207") (pin "1") (pinfunction "A_1") (pintype "passive"))
      (node (ref "S207") (pin "1") (pinfunction "1_1") (pintype "passive"))
    )
    (net (code "31") (name "Net-(D208-A)") (class "Default")
      (node (ref "D208") (pin "1") (pinfunction "A_1") (pintype "passive"))
      (node (ref "S208") (pin "1") (pinfunction "1_1") (pintype "passive"))
    )
    (net (code "32") (name "Net-(D209-A)") (class "Default")
      (node (ref "D209") (pin "1") (pinfunction "A_1") (pintype "passive"))
      (node (ref "S209") (pin "1") (pinfunction "1_1") (pintype "passive"))
    )
    (net (code "33") (name "Net-(D210-A)") (class "Default")
      (node (ref "D210") (pin "1") (pinfunction "A_1") (pintype "passive"))
      (node (ref "S210") (pin "1") (pinfunction "1_1") (pintype "passive"))
    )
    (net (code "34") (name "Net-(D211-A)") (class "Default")
      (node (ref "D211") (pin "1") (pinfunction "A_1") (pintype "passive"))
      (node (ref "S211") (pin "1") (pinfunction "1_1") (pintype "passive"))
    )
    (net (code "35") (name "Net-(D212-A)") (class "Default")
      (node (ref "D212") (pin "1") (pinfunction "A_1") (pintype "passive"))
      (node (ref "S212") (pin "1") (pinfunction "1_1") (pintype "passive"))
    )
    (net (code "36") (name "Net-(D213-A)") (class "Default")
      (node (ref "D213") (pin "1") (pinfunction "A_1") (pintype "passive"))
      (node (ref "S213") (pin "1") (pinfunction "1_1") (pintype "passive"))
    )
    (net (code "37") (name "Net-(D214-A)") (class "Default")
      (node (ref "D214") (pin "1") (pinfunction "A_1") (pintype "passive"))
      (node (ref "S214") (pin "1") (pinfunction "1_1") (pintype "passive"))
    )
    (net (code "38") (name "Net-(D215-A)") (class "Default")
      (node (ref "D215") (pin "1") (pinfunction "A_1") (pintype "passive"))
      (node (ref "S215") (pin "1") (pinfunction "1_1") (pintype "passive"))
    )
    (net (code "39") (name "Net-(D216-A)") (class "Default")
      (node (ref "D216") (pin "1") (pinfunction "A_1") (pintype "passive"))
      (node (ref "S216") (pin "1") (pinfunction "1_1") (pintype "passive"))
    )
    (net (code "40") (name "Net-(D217-A)") (class "Default")
      (node (ref "D217") (pin "1") (pinfunction "A_1") (pintype "passive"))
      (node (ref "S217") (pin "1") (pinfunction "1_1") (pintype "passive"))
    )
    (net (code "41") (name "Net-(D218-A)") (class "Default")
      (node (ref "D218") (pin "1") (pinfunction "A_1") (pintype "passive"))
      (node (ref "S218") (pin "1") (pinfunction "1_1") (pintype "passive"))
    )
    (net (code "42") (name "Net-(D219-A)") (class "Default")
      (node (ref "D219") (pin "1") (pinfunction "A_1") (pintype "passive"))
      (node (ref "S219") (pin "1") (pinfunction "1_1") (pintype "passive"))
    )
    (net (code "43") (name "Net-(D220-A)") (class "Default")
      (node (ref "D220") (pin "1") (pinfunction "A_1") (pintype "passive"))
      (node (ref "S220") (pin "1") (pinfunction "1_1") (pintype "passive"))
    )
    (net (code "44") (name "Net-(D221-A)") (class "Default")
      (node (ref "D221") (pin "1") (pinfunction "A_1") (pintype "passive"))
      (node (ref "S221") (pin "1") (pinfunction "1_1") (pintype "passive"))
    )
    (net (code "45") (name "Net-(D222-A)") (class "Default")
      (node (ref "D222") (pin "1") (pinfunction "A_1") (pintype "passive"))
      (node (ref "S222") (pin "1") (pinfunction "1_1") (pintype "passive"))
    )
    (net (code "46") (name "Net-(D223-A)") (class "Default")
      (node (ref "D223") (pin "1") (pinfunction "A_1") (pintype "passive"))
      (node (ref "S223") (pin "1") (pinfunction "1_1") (pintype "passive"))
    )
    (net (code "47") (name "Net-(D224-A)") (class "Default")
      (node (ref "D224") (pin "1") (pinfunction "A_1") (pintype "passive"))
      (node (ref "S224") (pin "1") (pinfunction "1_1") (pintype "passive"))
    )
    (net (code "48") (name "Net-(D225-A)") (class "Default")
      (node (ref "D225") (pin "1") (pinfunction "A_1") (pintype "passive"))
      (node (ref "S225") (pin "1") (pinfunction "1_1") (pintype "passive"))
    )
    (net (code "49") (name "Net-(D226-A)") (class "Default")
      (node (ref "D226") (pin "1") (pinfunction "A_1") (pintype "passive"))
      (node (ref "S226") (pin "1") (pinfunction "1_1") (pintype "passive"))
    )
    (net (code "50") (name "Net-(D227-A)") (class "Default")
      (node (ref "D227") (pin "1") (pinfunction "A_1") (pintype "passive"))
      (node (ref "S227") (pin "1") (pinfunction "1_1") (pintype "passive"))
    )
    (net (code "51") (name "Net-(D228-A)") (class "Default")
      (node (ref "D228") (pin "1") (pinfunction "A_1") (pintype "passive"))
      (node (ref "S228") (pin "1") (pinfunction "1_1") (pintype "passive"))
    )
    (net (code "52") (name "Net-(D229-A)") (class "Default")
      (node (ref "D229") (pin "1") (pinfunction "A_1") (pintype "passive"))
      (node (ref "S229") (pin "1") (pinfunction "1_1") (pintype "passive"))
    )
    (net (code "53") (name "Net-(D230-A)") (class "Default")
      (node (ref "D230") (pin "1") (pinfunction "A_1") (pintype "passive"))
      (node (ref "S230") (pin "1") (pinfunction "1_1") (pintype "passive"))
    )
    (net (code "54") (name "Net-(D231-A)") (class "Default")
      (node (ref "D231") (pin "1") (pinfunction "A_1") (pintype "passive"))
      (node (ref "S231") (pin "1") (pinfunction "1_1") (pintype "passive"))
    )
    (net (code "55") (name "Net-(D232-A)") (class "Default")
      (node (ref "D232") (pin "1") (pinfunction "A_1") (pintype "passive"))
      (node (ref "S232") (pin "1") (pinfunction "1_1") (pintype "passive"))
    )
    (net (code "56") (name "Net-(D233-A)") (class "Default")
      (node (ref "D233") (pin "1") (pinfunction "A_1") (pintype "passive"))
      (node (ref "S233") (pin "1") (pinfunction "1_1") (pintype "passive"))
    )
    (net (code "57") (name "Net-(D234-A)") (class "Default")
      (node (ref "D234") (pin "1") (pinfunction "A_1") (pintype "passive"))
      (node (ref "S234") (pin "2") (pinfunction "2_2") (pintype "passive"))
    )
    (net (code "58") (name "Net-(D235-A)") (class "Default")
      (node (ref "D235") (pin "1") (pinfunction "A_1") (pintype "passive"))
      (node (ref "S235") (pin "1") (pinfunction "1_1") (pintype "passive"))
    )
    (net (code "59") (name "Net-(D236-A)") (class "Default")
      (node (ref "D236") (pin "1") (pinfunction "A_1") (pintype "passive"))
      (node (ref "S236") (pin "1") (pinfunction "1_1") (pintype "passive"))
    )
    (net (code "60") (name "Net-(D237-A)") (class "Default")
      (node (ref "D237") (pin "1") (pinfunction "A_1") (pintype "passive"))
      (node (ref "S237") (pin "1") (pinfunction "1_1") (pintype "passive"))
    )
    (net (code "61") (name "Net-(D238-A)") (class "Default")
      (node (ref "D238") (pin "1") (pinfunction "A_1") (pintype "passive"))
      (node (ref "S238") (pin "1") (pinfunction "1_1") (pintype "passive"))
    )
    (net (code "62") (name "Net-(D239-A)") (class "Default")
      (node (ref "D239") (pin "1") (pinfunction "A_1") (pintype "passive"))
      (node (ref "S239") (pin "1") (pinfunction "1_1") (pintype "passive"))
    )
    (net (code "63") (name "Net-(D240-A)") (class "Default")
      (node (ref "D240") (pin "1") (pinfunction "A_1") (pintype "passive"))
      (node (ref "S240") (pin "1") (pinfunction "1_1") (pintype "passive"))
    )
    (net (code "64") (name "Net-(D241-A)") (class "Default")
      (node (ref "D241") (pin "1") (pinfunction "A_1") (pintype "passive"))
      (node (ref "S241") (pin "1") (pinfunction "1_1") (pintype "passive"))
    )
    (net (code "65") (name "Net-(D242-A)") (class "Default")
      (node (ref "D242") (pin "1") (pinfunction "A_1") (pintype "passive"))
      (node (ref "S242") (pin "1") (pinfunction "1_1") (pintype "passive"))
    )
    (net (code "66") (name "Net-(D243-A)") (class "Default")
      (node (ref "D243") (pin "1") (pinfunction "A_1") (pintype "passive"))
      (node (ref "S243") (pin "1") (pinfunction "1_1") (pintype "passive"))
    )
    (net (code "67") (name "Net-(D244-A)") (class "Default")
      (node (ref "D244") (pin "1") (pinfunction "A_1") (pintype "passive"))
      (node (ref "S244") (pin "1") (pinfunction "1_1") (pintype "passive"))
    )
    (net (code "68") (name "Net-(D245-A)") (class "Default")
      (node (ref "D245") (pin "1") (pinfunction "A_1") (pintype "passive"))
      (node (ref "S245") (pin "1") (pinfunction "1_1") (pintype "passive"))
    )
    (net (code "69") (name "Net-(D246-A)") (class "Default")
      (node (ref "D246") (pin "1") (pinfunction "A_1") (pintype "passive"))
      (node (ref "S246") (pin "1") (pinfunction "1_1") (pintype "passive"))
    )
    (net (code "70") (name "Net-(D247-A)") (class "Default")
      (node (ref "D247") (pin "1") (pinfunction "A_1") (pintype "passive"))
      (node (ref "S247") (pin "1") (pinfunction "1_1") (pintype "passive"))
    )
    (net (code "71") (name "Net-(D248-A)") (class "Default")
      (node (ref "D248") (pin "1") (pinfunction "A_1") (pintype "passive"))
      (node (ref "S248") (pin "1") (pinfunction "1_1") (pintype "passive"))
    )
    (net (code "72") (name "Net-(D249-A)") (class "Default")
      (node (ref "D249") (pin "1") (pinfunction "A_1") (pintype "passive"))
      (node (ref "S249") (pin "1") (pinfunction "1_1") (pintype "passive"))
    )
    (net (code "73") (name "Net-(D250-A)") (class "Default")
      (node (ref "D250") (pin "1") (pinfunction "A_1") (pintype "passive"))
      (node (ref "S250") (pin "1") (pinfunction "1_1") (pintype "passive"))
    )
    (net (code "74") (name "Net-(D251-A)") (class "Default")
      (node (ref "D251") (pin "1") (pinfunction "A_1") (pintype "passive"))
      (node (ref "S251") (pin "1") (pinfunction "1_1") (pintype "passive"))
    )
    (net (code "75") (name "Net-(D252-A)") (class "Default")
      (node (ref "D252") (pin "1") (pinfunction "A_1") (pintype "passive"))
      (node (ref "S252") (pin "1") (pinfunction "1_1") (pintype "passive"))
    )
    (net (code "76") (name "Net-(D253-A)") (class "Default")
      (node (ref "D253") (pin "1") (pinfunction "A_1") (pintype "passive"))
      (node (ref "S253") (pin "1") (pinfunction "1_1") (pintype "passive"))
    )
    (net (code "77") (name "Net-(D254-A)") (class "Default")
      (node (ref "D254") (pin "1") (pinfunction "A_1") (pintype "passive"))
      (node (ref "S254") (pin "1") (pinfunction "1_1") (pintype "passive"))
    )
    (net (code "78") (name "Net-(D255-A)") (class "Default")
      (node (ref "D255") (pin "1") (pinfunction "A_1") (pintype "passive"))
      (node (ref "S255") (pin "1") (pinfunction "1_1") (pintype "passive"))
    )
    (net (code "79") (name "Net-(D256-A)") (class "Default")
      (node (ref "D256") (pin "1") (pinfunction "A_1") (pintype "passive"))
      (node (ref "S256") (pin "1") (pinfunction "1_1") (pintype "passive"))
    )
    (net (code "80") (name "Net-(D257-A)") (class "Default")
      (node (ref "D257") (pin "1") (pinfunction "A_1") (pintype "passive"))
      (node (ref "S257") (pin "1") (pinfunction "1_1") (pintype "passive"))
    )
    (net (code "81") (name "Net-(D258-A)") (class "Default")
      (node (ref "D258") (pin "1") (pinfunction "A_1") (pintype "passive"))
      (node (ref "S258") (pin "1") (pinfunction "1_1") (pintype "passive"))
    )
    (net (code "82") (name "Net-(D259-A)") (class "Default")
      (node (ref "D259") (pin "1") (pinfunction "A_1") (pintype "passive"))
      (node (ref "S259") (pin "1") (pinfunction "1_1") (pintype "passive"))
    )
    (net (code "83") (name "Net-(D260-A)") (class "Default")
      (node (ref "D260") (pin "1") (pinfunction "A_1") (pintype "passive"))
      (node (ref "S260") (pin "1") (pinfunction "1_1") (pintype "passive"))
    )
    (net (code "84") (name "Net-(D261-A)") (class "Default")
      (node (ref "D261") (pin "1") (pinfunction "A_1") (pintype "passive"))
      (node (ref "S261") (pin "1") (pinfunction "1_1") (pintype "passive"))
    )
    (net (code "85") (name "Net-(D262-A)") (class "Default")
      (node (ref "D262") (pin "1") (pinfunction "A_1") (pintype "passive"))
      (node (ref "S262") (pin "1") (pinfunction "1_1") (pintype "passive"))
    )
    (net (code "86") (name "Net-(D263-A)") (class "Default")
      (node (ref "D263") (pin "1") (pinfunction "A_1") (pintype "passive"))
      (node (ref "S263") (pin "1") (pinfunction "1_1") (pintype "passive"))
    )
    (net (code "87") (name "Net-(D264-A)") (class "Default")
      (node (ref "D264") (pin "1") (pinfunction "A_1") (pintype "passive"))
      (node (ref "S264") (pin "1") (pinfunction "1_1") (pintype "passive"))
    )
    (net (code "88") (name "Net-(D265-A)") (class "Default")
      (node (ref "D265") (pin "1") (pinfunction "A_1") (pintype "passive"))
      (node (ref "S265") (pin "1") (pinfunction "1_1") (pintype "passive"))
    )
    (net (code "89") (name "Net-(D266-A)") (class "Default")
      (node (ref "D266") (pin "1") (pinfunction "A_1") (pintype "passive"))
      (node (ref "S266") (pin "1") (pinfunction "1_1") (pintype "passive"))
    )
    (net (code "90") (name "Net-(D267-A)") (class "Default")
      (node (ref "D267") (pin "1") (pinfunction "A_1") (pintype "passive"))
      (node (ref "S267") (pin "1") (pinfunction "1_1") (pintype "passive"))
    )
    (net (code "91") (name "Net-(D268-A)") (class "Default")
      (node (ref "D268") (pin "1") (pinfunction "A_1") (pintype "passive"))
      (node (ref "S268") (pin "1") (pinfunction "1_1") (pintype "passive"))
    )
    (net (code "92") (name "Net-(D269-A)") (class "Default")
      (node (ref "D269") (pin "1") (pinfunction "A_1") (pintype "passive"))
      (node (ref "S269") (pin "1") (pinfunction "1_1") (pintype "passive"))
    )
    (net (code "93") (name "Net-(D270-A)") (class "Default")
      (node (ref "D270") (pin "1") (pinfunction "A_1") (pintype "passive"))
      (node (ref "S270") (pin "1") (pinfunction "1_1") (pintype "passive"))
    )
    (net (code "94") (name "Net-(D271-A)") (class "Default")
      (node (ref "D271") (pin "1") (pinfunction "A_1") (pintype "passive"))
      (node (ref "S271") (pin "1") (pinfunction "1_1") (pintype "passive"))
    )
    (net (code "95") (name "Net-(D272-A)") (class "Default")
      (node (ref "D272") (pin "1") (pinfunction "A_1") (pintype "passive"))
      (node (ref "S272") (pin "1") (pinfunction "1_1") (pintype "passive"))
    )
    (net (code "96") (name "Net-(D273-A)") (class "Default")
      (node (ref "D273") (pin "1") (pinfunction "A_1") (pintype "passive"))
      (node (ref "S273") (pin "1") (pinfunction "1_1") (pintype "passive"))
    )
    (net (code "97") (name "Net-(D274-A)") (class "Default")
      (node (ref "D274") (pin "1") (pinfunction "A_1") (pintype "passive"))
      (node (ref "S274") (pin "1") (pinfunction "1_1") (pintype "passive"))
    )
    (net (code "98") (name "Net-(D275-A)") (class "Default")
      (node (ref "D275") (pin "1") (pinfunction "A_1") (pintype "passive"))
      (node (ref "S275") (pin "1") (pinfunction "1_1") (pintype "passive"))
    )
    (net (code "99") (name "Net-(D276-A)") (class "Default")
      (node (ref "D276") (pin "1") (pinfunction "A_1") (pintype "passive"))
      (node (ref "S276") (pin "1") (pinfunction "1_1") (pintype "passive"))
    )
    (net (code "100") (name "Net-(D277-A)") (class "Default")
      (node (ref "D277") (pin "1") (pinfunction "A_1") (pintype "passive"))
      (node (ref "S277") (pin "1") (pinfunction "1_1") (pintype "passive"))
    )
    (net (code "101") (name "Net-(D278-A)") (class "Default")
      (node (ref "D278") (pin "1") (pinfunction "A_1") (pintype "passive"))
      (node (ref "S278") (pin "1") (pinfunction "1_1") (pintype "passive"))
    )
    (net (code "102") (name "Net-(D279-A)") (class "Default")
      (node (ref "D279") (pin "1") (pinfunction "A_1") (pintype "passive"))
      (node (ref "S279") (pin "1") (pinfunction "1_1") (pintype "passive"))
    )
    (net (code "103") (name "Net-(D280-A)") (class "Default")
      (node (ref "D280") (pin "1") (pinfunction "A_1") (pintype "passive"))
      (node (ref "S280") (pin "2") (pinfunction "2_2") (pintype "passive"))
    )
    (net (code "104") (name "Net-(D281-A)") (class "Default")
      (node (ref "D281") (pin "1") (pinfunction "A_1") (pintype "passive"))
      (node (ref "S281") (pin "1") (pinfunction "1_1") (pintype "passive"))
    )
    (net (code "105") (name "Net-(D282-A)") (class "Default")
      (node (ref "D282") (pin "1") (pinfunction "A_1") (pintype "passive"))
      (node (ref "S282") (pin "1") (pinfunction "1_1") (pintype "passive"))
    )
    (net (code "106") (name "Net-(D283-A)") (class "Default")
      (node (ref "D283") (pin "1") (pinfunction "A_1") (pintype "passive"))
      (node (ref "S283") (pin "1") (pinfunction "1_1") (pintype "passive"))
    )
    (net (code "107") (name "Net-(D284-A)") (class "Default")
      (node (ref "D284") (pin "1") (pinfunction "A_1") (pintype "passive"))
      (node (ref "S284") (pin "1") (pinfunction "1_1") (pintype "passive"))
    )
    (net (code "108") (name "Net-(D285-A)") (class "Default")
      (node (ref "D285") (pin "1") (pinfunction "A_1") (pintype "passive"))
      (node (ref "S285") (pin "1") (pinfunction "1_1") (pintype "passive"))
    )
    (net (code "109") (name "Net-(D286-A)") (class "Default")
      (node (ref "D286") (pin "1") (pinfunction "A_1") (pintype "passive"))
      (node (ref "S286") (pin "1") (pinfunction "1_1") (pintype "passive"))
    )
    (net (code "110") (name "Net-(D287-A)") (class "Default")
      (node (ref "D287") (pin "1") (pinfunction "A_1") (pintype "passive"))
      (node (ref "S287") (pin "1") (pinfunction "1_1") (pintype "passive"))
    )
    (net (code "111") (name "Net-(D288-A)") (class "Default")
      (node (ref "D288") (pin "1") (pinfunction "A_1") (pintype "passive"))
      (node (ref "S288") (pin "1") (pinfunction "1_1") (pintype "passive"))
    )
    (net (code "112") (name "Net-(D289-A)") (class "Default")
      (node (ref "D289") (pin "1") (pinfunction "A_1") (pintype "passive"))
      (node (ref "S289") (pin "1") (pinfunction "1_1") (pintype "passive"))
    )
  )
)
